# top.net
KiCad netlist of a schematic drawn in Altium Designer
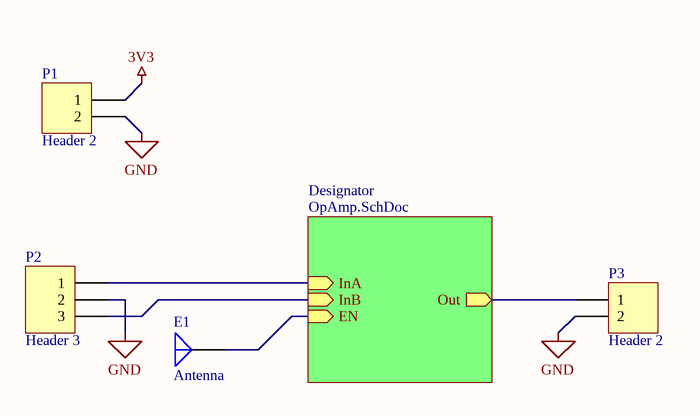
[diagram p0: top.SchDoc]

(export (version "E")
  (design (tool "Eeschema 10.0.6"))
  (components
    (comp (ref "E1")
      (value "Antenna")
      (footprint "PIN1")
      (description "Generic Antenna")
      (fields (field (name "PUBLISHER") "Altium Limited"))
      (libsource (lib "Miscellaneous Devices") (part "Antenna"))
    )
    (comp (ref "P1")
      (value "Header 2")
      (footprint "HEADER 1X2 Male")
      (description "Header, 2-Pin")
      (fields (field (name "PUBLISHER") "Altium Limited"))
      (libsource (lib "") (part "Header 2_1"))
    )
    (comp (ref "P2")
      (value "Header 3")
      (footprint "HEADER 1X3 MALE")
      (description "Header, 3-Pin")
      (fields (field (name "PUBLISHER") "Altium Limited"))
      (libsource (lib "_Connectors") (part "Header 3"))
    )
    (comp (ref "P3")
      (value "Header 2")
      (footprint "HEADER 1X2 Male")
      (description "Header, 2-Pin")
      (fields (field (name "PUBLISHER") "Altium Limited"))
      (libsource (lib "_Connectors") (part "Header 2"))
    )
  )
  (nets
    (net (code "1") (name "/EN") (class "Default")
      (node (ref "E1") (pin "1") (pinfunction "A_1") (pintype "passive"))
    )
    (net (code "2") (name "/InA") (class "Default")
      (node (ref "P2") (pin "1") (pinfunction "1_1") (pintype "passive"))
    )
    (net (code "3") (name "/InB") (class "Default")
      (node (ref "P2") (pin "3") (pinfunction "3_3") (pintype "passive"))
    )
    (net (code "4") (name "/Out") (class "Default")
      (node (ref "P3") (pin "1") (pinfunction "1_1") (pintype "passive"))
    )
    (net (code "5") (name "3V3") (class "Default")
      (node (ref "P1") (pin "1") (pinfunction "1_1") (pintype "passive"))
    )
    (net (code "6") (name "GND") (class "Default")
      (node (ref "P1") (pin "2") (pinfunction "2_2") (pintype "passive"))
      (node (ref "P2") (pin "2") (pinfunction "2_2") (pintype "passive"))
      (node (ref "P3") (pin "2") (pinfunction "2_2") (pintype "passive"))
    )
  )
)
